# PCB-Tester-Board-V1.net
KiCad netlist of a schematic drawn in Altium Designer
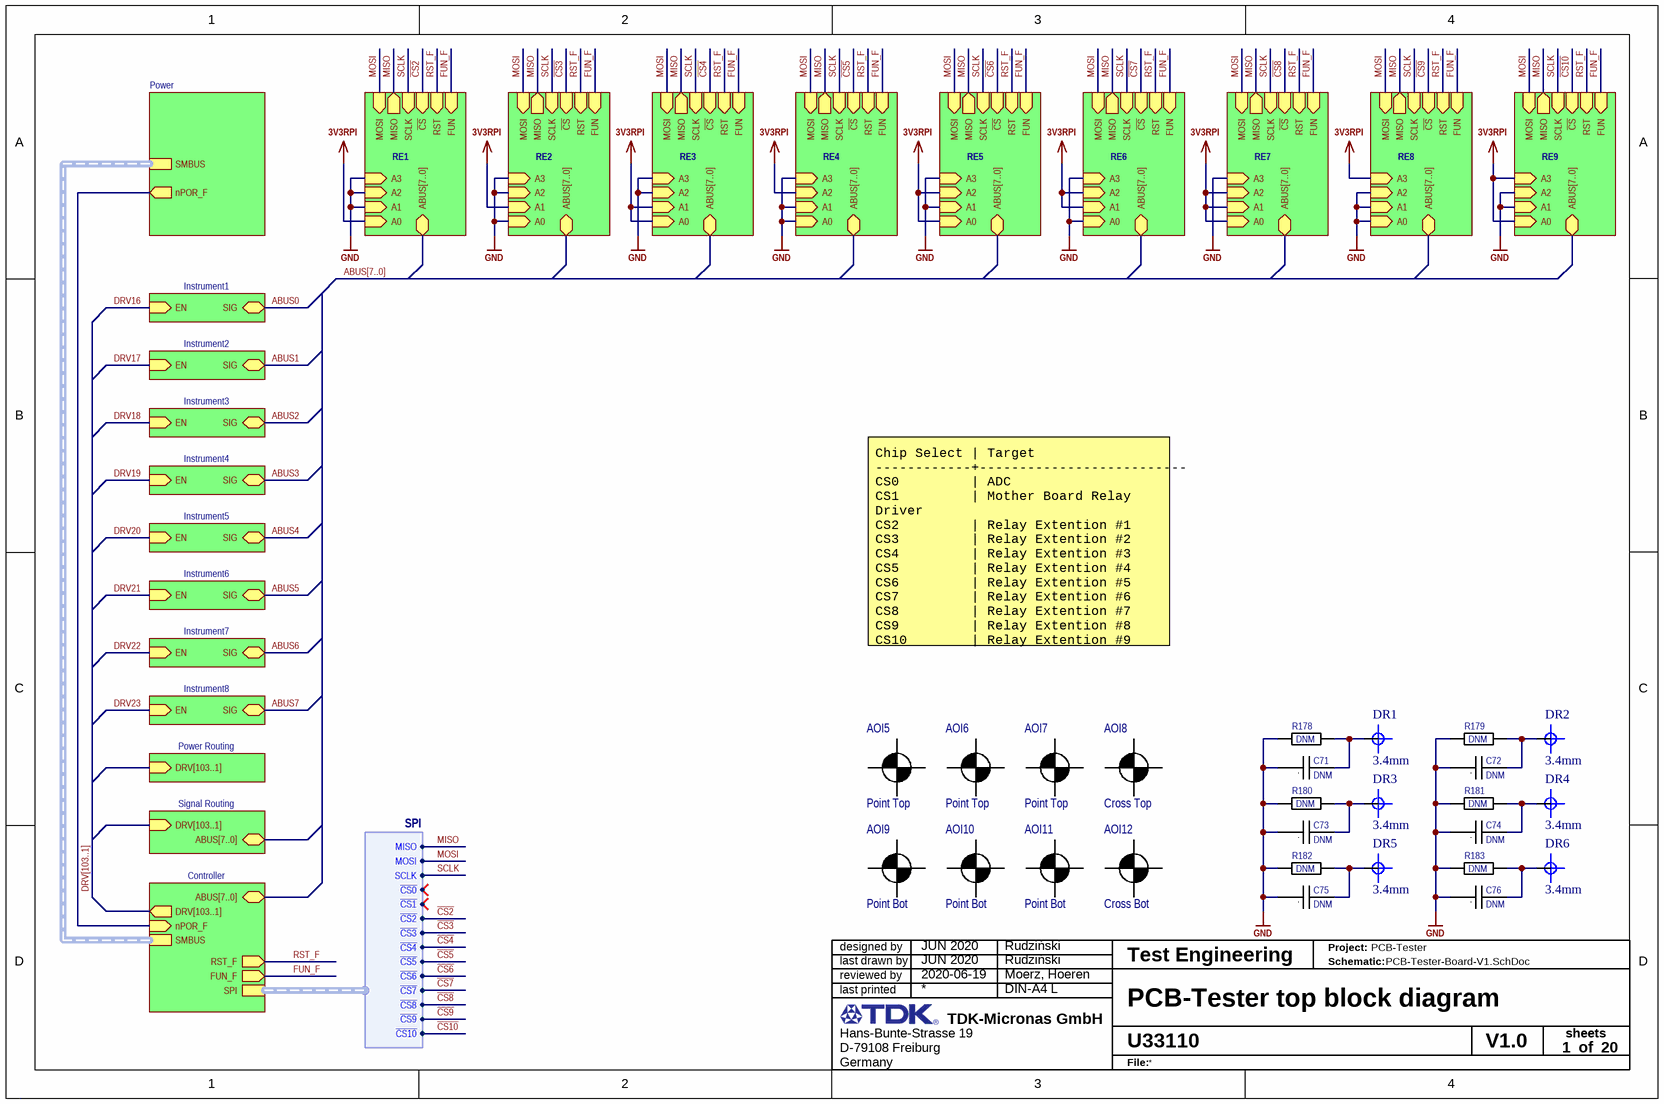
[diagram p0: PCB-Tester-Board-V1.SchDoc]

(export (version "E")
  (design (tool "Eeschema 10.0.6"))
  (components
    (comp (ref "AOI5")
      (value "AOI")
      (footprint "Fiducial Point")
      (description "Assembly AOI")
      (fields (field (name "SHAPE") "Point Top") (field (name "13. CREATED DATE/NAME") "AUG2018/Hören"))
      (libsource (lib "PCB-Tester-Board-V1") (part "Fiducial"))
    )
    (comp (ref "AOI6")
      (value "AOI")
      (footprint "Fiducial Point")
      (description "Assembly AOI")
      (fields (field (name "SHAPE") "Point Top") (field (name "13. CREATED DATE/NAME") "AUG2018/Hören"))
      (libsource (lib "PCB-Tester-Board-V1") (part "Fiducial"))
    )
    (comp (ref "AOI7")
      (value "AOI")
      (footprint "Fiducial Point")
      (description "Assembly AOI")
      (fields (field (name "SHAPE") "Point Top") (field (name "13. CREATED DATE/NAME") "AUG2018/Hören"))
      (libsource (lib "PCB-Tester-Board-V1") (part "Fiducial"))
    )
    (comp (ref "AOI8")
      (value "AOI")
      (footprint "Fiducial Cross")
      (description "Assembly AOI")
      (fields (field (name "SHAPE") "Cross Top") (field (name "13. CREATED DATE/NAME") "AUG2018/Hören"))
      (libsource (lib "PCB-Tester-Board-V1") (part "Fiducial"))
    )
    (comp (ref "AOI9")
      (value "AOI")
      (footprint "Fiducial Point")
      (description "Assembly AOI")
      (fields (field (name "SHAPE") "Point Bot") (field (name "13. CREATED DATE/NAME") "AUG2018/Hören"))
      (libsource (lib "PCB-Tester-Board-V1") (part "Fiducial"))
    )
    (comp (ref "AOI10")
      (value "AOI")
      (footprint "Fiducial Point")
      (description "Assembly AOI")
      (fields (field (name "SHAPE") "Point Bot") (field (name "13. CREATED DATE/NAME") "AUG2018/Hören"))
      (libsource (lib "PCB-Tester-Board-V1") (part "Fiducial"))
    )
    (comp (ref "AOI11")
      (value "AOI")
      (footprint "Fiducial Point")
      (description "Assembly AOI")
      (fields (field (name "SHAPE") "Point Bot") (field (name "13. CREATED DATE/NAME") "AUG2018/Hören"))
      (libsource (lib "PCB-Tester-Board-V1") (part "Fiducial"))
    )
    (comp (ref "AOI12")
      (value "AOI")
      (footprint "Fiducial Cross")
      (description "Assembly AOI")
      (fields (field (name "SHAPE") "Cross Bot") (field (name "13. CREATED DATE/NAME") "AUG2018/Hören"))
      (libsource (lib "PCB-Tester-Board-V1") (part "Fiducial"))
    )
    (comp (ref "C71")
      (value "DNM")
      (footprint "C1206 Reflow")
      (description "Capacitor Unpolarized")
      (fields
        (field (name "TOLERANCE") "±20%")
        (field (name "Comment") "C")
        (field (name "13. CREATED DATE/NAME") "AUG2018/Hören")
      )
      (libsource (lib "chickenfood") (part "C"))
    )
    (comp (ref "C72")
      (value "DNM")
      (footprint "C1206 Reflow")
      (description "Capacitor Unpolarized")
      (fields
        (field (name "TOLERANCE") "±20%")
        (field (name "Comment") "C")
        (field (name "13. CREATED DATE/NAME") "AUG2018/Hören")
      )
      (libsource (lib "chickenfood") (part "C"))
    )
    (comp (ref "C73")
      (value "DNM")
      (footprint "C1206 Reflow")
      (description "Capacitor Unpolarized")
      (fields
        (field (name "TOLERANCE") "±20%")
        (field (name "Comment") "C")
        (field (name "13. CREATED DATE/NAME") "AUG2018/Hören")
      )
      (libsource (lib "chickenfood") (part "C"))
    )
    (comp (ref "C74")
      (value "DNM")
      (footprint "C1206 Reflow")
      (description "Capacitor Unpolarized")
      (fields
        (field (name "TOLERANCE") "±20%")
        (field (name "Comment") "C")
        (field (name "13. CREATED DATE/NAME") "AUG2018/Hören")
      )
      (libsource (lib "chickenfood") (part "C"))
    )
    (comp (ref "C75")
      (value "DNM")
      (footprint "C1206 Reflow")
      (description "Capacitor Unpolarized")
      (fields
        (field (name "TOLERANCE") "±20%")
        (field (name "Comment") "C")
        (field (name "13. CREATED DATE/NAME") "AUG2018/Hören")
      )
      (libsource (lib "chickenfood") (part "C"))
    )
    (comp (ref "C76")
      (value "DNM")
      (footprint "C1206 Reflow")
      (description "Capacitor Unpolarized")
      (fields
        (field (name "TOLERANCE") "±20%")
        (field (name "Comment") "C")
        (field (name "13. CREATED DATE/NAME") "AUG2018/Hören")
      )
      (libsource (lib "chickenfood") (part "C"))
    )
    (comp (ref "DR1")
      (value "3.4mm")
      (footprint "HOLE_3.4mm")
      (description "Fiducal 90 mil")
      (libsource (lib "SchLib1") (part "Drill-3.2mm-M3-C"))
    )
    (comp (ref "DR2")
      (value "3.4mm")
      (footprint "HOLE_3.4mm")
      (description "Fiducal 90 mil")
      (libsource (lib "SchLib1") (part "Drill-3.2mm-M3-C"))
    )
    (comp (ref "DR3")
      (value "3.4mm")
      (footprint "HOLE_3.4mm")
      (description "Fiducal 90 mil")
      (libsource (lib "SchLib1") (part "Drill-3.2mm-M3-C"))
    )
    (comp (ref "DR4")
      (value "3.4mm")
      (footprint "HOLE_3.4mm")
      (description "Fiducal 90 mil")
      (libsource (lib "SchLib1") (part "Drill-3.2mm-M3-C"))
    )
    (comp (ref "DR5")
      (value "3.4mm")
      (footprint "HOLE_3.4mm")
      (description "Fiducal 90 mil")
      (libsource (lib "SchLib1") (part "Drill-3.2mm-M3-C"))
    )
    (comp (ref "DR6")
      (value "3.4mm")
      (footprint "HOLE_3.4mm")
      (description "Fiducal 90 mil")
      (libsource (lib "SchLib1") (part "Drill-3.2mm-M3-C"))
    )
    (comp (ref "R178")
      (value "DNM")
      (footprint "R1206 Reflow")
      (description "Resistor")
      (fields
        (field (name "TOLERANCE") "±1%")
        (field (name "Comment") "R")
        (field (name "13. CREATED DATE/NAME") "AUG2018/Hören")
      )
      (libsource (lib "chickenfood") (part "R"))
    )
    (comp (ref "R179")
      (value "DNM")
      (footprint "R1206 Reflow")
      (description "Resistor")
      (fields
        (field (name "TOLERANCE") "±1%")
        (field (name "Comment") "R")
        (field (name "13. CREATED DATE/NAME") "AUG2018/Hören")
      )
      (libsource (lib "chickenfood") (part "R"))
    )
    (comp (ref "R180")
      (value "DNM")
      (footprint "R1206 Reflow")
      (description "Resistor")
      (fields
        (field (name "TOLERANCE") "±1%")
        (field (name "Comment") "R")
        (field (name "13. CREATED DATE/NAME") "AUG2018/Hören")
      )
      (libsource (lib "chickenfood") (part "R"))
    )
    (comp (ref "R181")
      (value "DNM")
      (footprint "R1206 Reflow")
      (description "Resistor")
      (fields
        (field (name "TOLERANCE") "±1%")
        (field (name "Comment") "R")
        (field (name "13. CREATED DATE/NAME") "AUG2018/Hören")
      )
      (libsource (lib "chickenfood") (part "R"))
    )
    (comp (ref "R182")
      (value "DNM")
      (footprint "R1206 Reflow")
      (description "Resistor")
      (fields
        (field (name "TOLERANCE") "±1%")
        (field (name "Comment") "R")
        (field (name "13. CREATED DATE/NAME") "AUG2018/Hören")
      )
      (libsource (lib "chickenfood") (part "R"))
    )
    (comp (ref "R183")
      (value "DNM")
      (footprint "R1206 Reflow")
      (description "Resistor")
      (fields
        (field (name "TOLERANCE") "±1%")
        (field (name "Comment") "R")
        (field (name "13. CREATED DATE/NAME") "AUG2018/Hören")
      )
      (libsource (lib "chickenfood") (part "R"))
    )
  )
  (nets
    (net (code "143") (name "GND") (class "Default")
      (node (ref "C71") (pin "1") (pinfunction "1_1") (pintype "passive"))
      (node (ref "C72") (pin "1") (pinfunction "1_1") (pintype "passive"))
      (node (ref "C73") (pin "1") (pinfunction "1_1") (pintype "passive"))
      (node (ref "C74") (pin "1") (pinfunction "1_1") (pintype "passive"))
      (node (ref "C75") (pin "1") (pinfunction "1_1") (pintype "passive"))
      (node (ref "C76") (pin "1") (pinfunction "1_1") (pintype "passive"))
      (node (ref "R178") (pin "2") (pinfunction "2_2") (pintype "passive"))
      (node (ref "R179") (pin "2") (pinfunction "2_2") (pintype "passive"))
      (node (ref "R180") (pin "2") (pinfunction "2_2") (pintype "passive"))
      (node (ref "R181") (pin "2") (pinfunction "2_2") (pintype "passive"))
      (node (ref "R182") (pin "2") (pinfunction "2_2") (pintype "passive"))
      (node (ref "R183") (pin "2") (pinfunction "2_2") (pintype "passive"))
    )
    (net (code "144") (name "Net-(DR1-OUT3)") (class "Default")
      (node (ref "C71") (pin "2") (pinfunction "2_2") (pintype "passive"))
      (node (ref "DR1") (pin "1") (pinfunction "OUT3_1") (pintype "passive"))
      (node (ref "R178") (pin "1") (pinfunction "1_1") (pintype "passive"))
    )
    (net (code "145") (name "Net-(DR2-OUT3)") (class "Default")
      (node (ref "C72") (pin "2") (pinfunction "2_2") (pintype "passive"))
      (node (ref "DR2") (pin "1") (pinfunction "OUT3_1") (pintype "passive"))
      (node (ref "R179") (pin "1") (pinfunction "1_1") (pintype "passive"))
    )
    (net (code "146") (name "Net-(DR3-OUT3)") (class "Default")
      (node (ref "C73") (pin "2") (pinfunction "2_2") (pintype "passive"))
      (node (ref "DR3") (pin "1") (pinfunction "OUT3_1") (pintype "passive"))
      (node (ref "R180") (pin "1") (pinfunction "1_1") (pintype "passive"))
    )
    (net (code "147") (name "Net-(DR4-OUT3)") (class "Default")
      (node (ref "C74") (pin "2") (pinfunction "2_2") (pintype "passive"))
      (node (ref "DR4") (pin "1") (pinfunction "OUT3_1") (pintype "passive"))
      (node (ref "R181") (pin "1") (pinfunction "1_1") (pintype "passive"))
    )
    (net (code "148") (name "Net-(DR5-OUT3)") (class "Default")
      (node (ref "C75") (pin "2") (pinfunction "2_2") (pintype "passive"))
      (node (ref "DR5") (pin "1") (pinfunction "OUT3_1") (pintype "passive"))
      (node (ref "R182") (pin "1") (pinfunction "1_1") (pintype "passive"))
    )
    (net (code "149") (name "Net-(DR6-OUT3)") (class "Default")
      (node (ref "C76") (pin "2") (pinfunction "2_2") (pintype "passive"))
      (node (ref "DR6") (pin "1") (pinfunction "OUT3_1") (pintype "passive"))
      (node (ref "R183") (pin "1") (pinfunction "1_1") (pintype "passive"))
    )
  )
)
